# DXL_Bus.net
KiCad netlist of a schematic drawn in Altium Designer
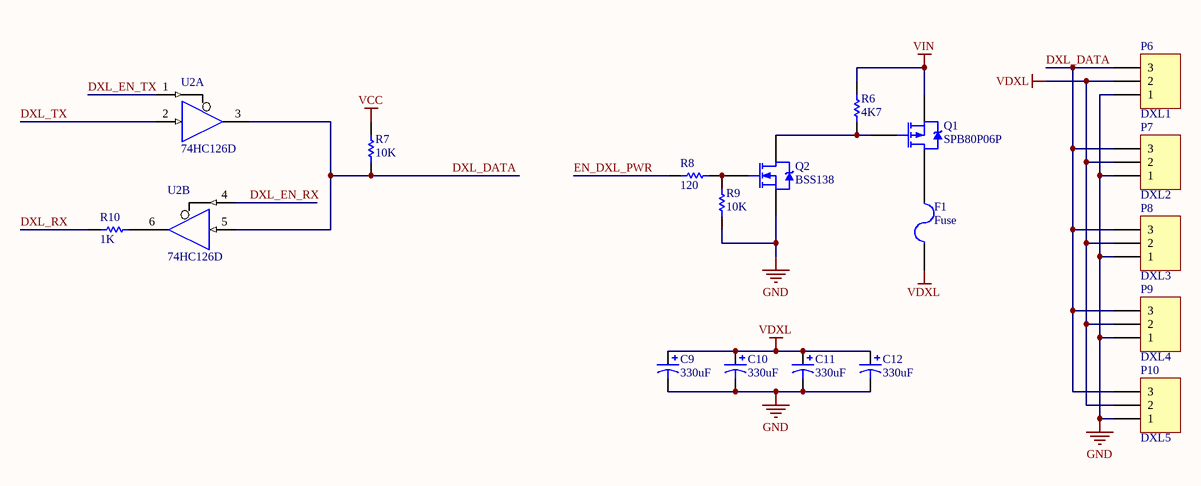
[diagram p0: DXL Bus.SchDoc]

(export (version "E")
  (design (tool "Eeschema 10.0.6"))
  (components
    (comp (ref "C9")
      (value "330uF")
      (footprint "SV-C")
      (description "Polarized Capacitor (Axial)")
      (fields (field (name "PUBLISHER") "Altium Limited"))
      (libsource (lib "BarelangRobotics") (part "Cap Pol"))
    )
    (comp (ref "C10")
      (value "330uF")
      (footprint "SV-C")
      (description "Polarized Capacitor (Axial)")
      (fields (field (name "PUBLISHER") "Altium Limited"))
      (libsource (lib "BarelangRobotics") (part "Cap Pol"))
    )
    (comp (ref "C11")
      (value "330uF")
      (footprint "SV-C")
      (description "Polarized Capacitor (Axial)")
      (fields (field (name "PUBLISHER") "Altium Limited"))
      (libsource (lib "BarelangRobotics") (part "Cap Pol"))
    )
    (comp (ref "C12")
      (value "330uF")
      (footprint "SV-C")
      (description "Polarized Capacitor (Axial)")
      (fields (field (name "PUBLISHER") "Altium Limited"))
      (libsource (lib "BarelangRobotics") (part "Cap Pol"))
    )
    (comp (ref "F1")
      (value "Fuse")
      (footprint "FUSE-HOLDER-SMD")
      (fields (field (name "PUBLISHER") "Altium Limited"))
      (libsource (lib "BarelangRobotics") (part "Fuse"))
    )
    (comp (ref "P6")
      (value "DXL1")
      (footprint "DXL")
      (description "Header, 3-Pin")
      (fields (field (name "PUBLISHER") "Altium Limited"))
      (libsource (lib "BarelangRobotics") (part "Header 3"))
    )
    (comp (ref "P7")
      (value "DXL2")
      (footprint "DXL")
      (description "Header, 3-Pin")
      (fields (field (name "PUBLISHER") "Altium Limited"))
      (libsource (lib "BarelangRobotics") (part "Header 3"))
    )
    (comp (ref "P8")
      (value "DXL3")
      (footprint "DXL")
      (description "Header, 3-Pin")
      (fields (field (name "PUBLISHER") "Altium Limited"))
      (libsource (lib "BarelangRobotics") (part "Header 3"))
    )
    (comp (ref "P9")
      (value "DXL4")
      (footprint "DXL")
      (description "Header, 3-Pin")
      (fields (field (name "PUBLISHER") "Altium Limited"))
      (libsource (lib "BarelangRobotics") (part "Header 3"))
    )
    (comp (ref "P10")
      (value "DXL5")
      (footprint "DXL")
      (description "Header, 3-Pin")
      (fields (field (name "PUBLISHER") "Altium Limited"))
      (libsource (lib "BarelangRobotics") (part "Header 3"))
    )
    (comp (ref "Q1")
      (value "SPB80P06P")
      (footprint "TO263")
      (description "P-Channel Power MOSFET")
      (fields (field (name "PUBLISHER") "Altium Limited"))
      (libsource (lib "BarelangRobotics") (part "PMOS"))
    )
    (comp (ref "Q2")
      (value "BSS138")
      (footprint "SOT23")
      (description "N-Channel Power MOSFET")
      (fields (field (name "PUBLISHER") "Altium Limited"))
      (libsource (lib "BarelangRobotics") (part "NMOS"))
    )
    (comp (ref "R6")
      (value "4K7")
      (footprint "0603-RES")
      (description "Resistor")
      (fields (field (name "PUBLISHER") "Altium Limited"))
      (libsource (lib "BarelangRobotics") (part "Res"))
    )
    (comp (ref "R7")
      (value "10K")
      (footprint "0603-RES")
      (description "Resistor")
      (fields (field (name "PUBLISHER") "Altium Limited"))
      (libsource (lib "BarelangRobotics") (part "Res"))
    )
    (comp (ref "R8")
      (value "120")
      (footprint "0603-RES")
      (description "Resistor")
      (fields (field (name "PUBLISHER") "Altium Limited"))
      (libsource (lib "BarelangRobotics") (part "Res"))
    )
    (comp (ref "R9")
      (value "10K")
      (footprint "0603-RES")
      (description "Resistor")
      (fields (field (name "PUBLISHER") "Altium Limited"))
      (libsource (lib "BarelangRobotics") (part "Res"))
    )
    (comp (ref "R10")
      (value "1K")
      (footprint "0603-RES")
      (description "Resistor")
      (fields (field (name "PUBLISHER") "Altium Limited"))
      (libsource (lib "BarelangRobotics") (part "Res"))
    )
    (comp (ref "U2")
      (value "74HC126D")
      (footprint "14-SOIC")
      (description "Quadruple Bus Buffer Gate with 3-State Outputs")
      (fields (field (name "PUBLISHER") "Altium Limited"))
      (libsource (lib "BarelangRobotics") (part "74HC126D"))
    )
  )
  (nets
    (net (code "1") (name "/DXL_DATA") (class "Default")
      (node (ref "P10") (pin "3") (pinfunction "3_3") (pintype "passive"))
      (node (ref "P6") (pin "3") (pinfunction "3_3") (pintype "passive"))
      (node (ref "P7") (pin "3") (pinfunction "3_3") (pintype "passive"))
      (node (ref "P8") (pin "3") (pinfunction "3_3") (pintype "passive"))
      (node (ref "P9") (pin "3") (pinfunction "3_3") (pintype "passive"))
      (node (ref "R7") (pin "1") (pinfunction "1_1") (pintype "passive"))
      (node (ref "U2") (pin "3") (pinfunction "Y_3") (pintype "tri_state"))
      (node (ref "U2") (pin "5") (pinfunction "A_5") (pintype "input"))
    )
    (net (code "2") (name "/DXL_EN_RX") (class "Default")
      (node (ref "U2") (pin "4") (pinfunction "OE_4") (pintype "input"))
    )
    (net (code "3") (name "/DXL_EN_TX") (class "Default")
      (node (ref "U2") (pin "1") (pinfunction "OE_1") (pintype "input"))
    )
    (net (code "4") (name "/DXL_RX") (class "Default")
      (node (ref "R10") (pin "1") (pinfunction "1_1") (pintype "passive"))
    )
    (net (code "5") (name "/DXL_TX") (class "Default")
      (node (ref "U2") (pin "2") (pinfunction "A_2") (pintype "input"))
    )
    (net (code "6") (name "/EN_DXL_PWR") (class "Default")
      (node (ref "R8") (pin "1") (pinfunction "1_1") (pintype "passive"))
    )
    (net (code "7") (name "GND") (class "Default")
      (node (ref "C10") (pin "2") (pinfunction "2_2") (pintype "passive"))
      (node (ref "C11") (pin "2") (pinfunction "2_2") (pintype "passive"))
      (node (ref "C12") (pin "2") (pinfunction "2_2") (pintype "passive"))
      (node (ref "C9") (pin "2") (pinfunction "2_2") (pintype "passive"))
      (node (ref "P10") (pin "1") (pinfunction "1_1") (pintype "passive"))
      (node (ref "P6") (pin "1") (pinfunction "1_1") (pintype "passive"))
      (node (ref "P7") (pin "1") (pinfunction "1_1") (pintype "passive"))
      (node (ref "P8") (pin "1") (pinfunction "1_1") (pintype "passive"))
      (node (ref "P9") (pin "1") (pinfunction "1_1") (pintype "passive"))
      (node (ref "Q2") (pin "2") (pinfunction "S_2") (pintype "passive"))
      (node (ref "R9") (pin "1") (pinfunction "1_1") (pintype "passive"))
      (node (ref "U2") (pin "7") (pinfunction "GND_7") (pintype "power_in"))
    )
    (net (code "8") (name "Net-(Q1-D)") (class "Default")
      (node (ref "F1") (pin "2") (pinfunction "2_2") (pintype "passive"))
      (node (ref "Q1") (pin "2") (pinfunction "D_2") (pintype "passive"))
    )
    (net (code "9") (name "Net-(Q1-G)") (class "Default")
      (node (ref "Q1") (pin "1") (pinfunction "G_1") (pintype "passive"))
      (node (ref "Q2") (pin "3") (pinfunction "D_3") (pintype "passive"))
      (node (ref "R6") (pin "1") (pinfunction "1_1") (pintype "passive"))
    )
    (net (code "10") (name "Net-(Q2-G)") (class "Default")
      (node (ref "Q2") (pin "1") (pinfunction "G_1") (pintype "passive"))
      (node (ref "R8") (pin "2") (pinfunction "2_2") (pintype "passive"))
      (node (ref "R9") (pin "2") (pinfunction "2_2") (pintype "passive"))
    )
    (net (code "11") (name "Net-(U2B-Y)") (class "Default")
      (node (ref "R10") (pin "2") (pinfunction "2_2") (pintype "passive"))
      (node (ref "U2") (pin "6") (pinfunction "Y_6") (pintype "tri_state"))
    )
    (net (code "12") (name "VCC") (class "Default")
      (node (ref "R7") (pin "2") (pinfunction "2_2") (pintype "passive"))
      (node (ref "U2") (pin "14") (pinfunction "VCC_14") (pintype "power_in"))
    )
    (net (code "13") (name "VDXL") (class "Default")
      (node (ref "C10") (pin "1") (pinfunction "1_1") (pintype "passive"))
      (node (ref "C11") (pin "1") (pinfunction "1_1") (pintype "passive"))
      (node (ref "C12") (pin "1") (pinfunction "1_1") (pintype "passive"))
      (node (ref "C9") (pin "1") (pinfunction "1_1") (pintype "passive"))
      (node (ref "F1") (pin "1") (pinfunction "1_1") (pintype "passive"))
      (node (ref "P10") (pin "2") (pinfunction "2_2") (pintype "passive"))
      (node (ref "P6") (pin "2") (pinfunction "2_2") (pintype "passive"))
      (node (ref "P7") (pin "2") (pinfunction "2_2") (pintype "passive"))
      (node (ref "P8") (pin "2") (pinfunction "2_2") (pintype "passive"))
      (node (ref "P9") (pin "2") (pinfunction "2_2") (pintype "passive"))
    )
    (net (code "14") (name "VIN") (class "Default")
      (node (ref "Q1") (pin "3") (pinfunction "S_3") (pintype "passive"))
      (node (ref "R6") (pin "2") (pinfunction "2_2") (pintype "passive"))
    )
  )
)
